# Ref_CLK.net
KiCad netlist of a schematic drawn in Altium Designer
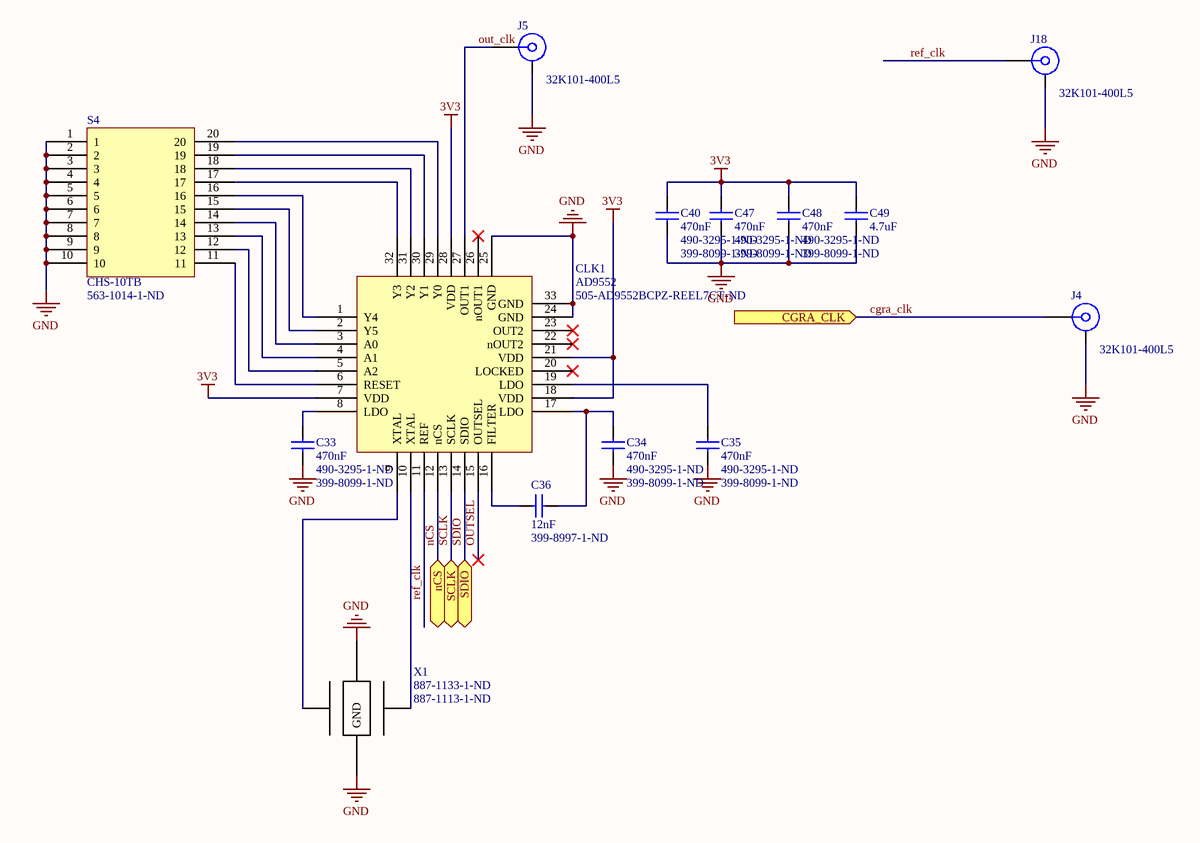
[diagram p0: Ref_CLK.SchDoc]

(export (version "E")
  (design (tool "Eeschema 10.0.6"))
  (components
    (comp (ref "C33")
      (value "CAP_470nF_1608mm_0603mil_1")
      (footprint "CAPC1005X06N")
      (description "0.47uF Capacitor")
      (fields
        (field (name "MANUFACTURER") "Murata")
        (field (name "MANUFACTURER PART NUMBER") "GRM155R61E225ME15D")
        (field (name "CAPACITANCE") "470nF")
        (field (name "SUPPLIER PART NUMBER 1") "490-3295-1-ND")
        (field (name "SUPPLIER PART NUMBER 2") "399-8099-1-ND")
      )
      (libsource (lib "CGRA_schlib") (part "CAP_470nF_1608mm_0603mil_1"))
    )
    (comp (ref "C34")
      (value "CAP_470nF_1608mm_0603mil_1")
      (footprint "CAPC1005X06N")
      (description "0.47uF Capacitor")
      (fields
        (field (name "MANUFACTURER") "Murata")
        (field (name "MANUFACTURER PART NUMBER") "GRM155R61E225ME15D")
        (field (name "CAPACITANCE") "470nF")
        (field (name "SUPPLIER PART NUMBER 1") "490-3295-1-ND")
        (field (name "SUPPLIER PART NUMBER 2") "399-8099-1-ND")
      )
      (libsource (lib "CGRA_schlib") (part "CAP_470nF_1608mm_0603mil_1"))
    )
    (comp (ref "C35")
      (value "CAP_470nF_1608mm_0603mil_1")
      (footprint "CAPC1005X06N")
      (description "0.47uF Capacitor")
      (fields
        (field (name "MANUFACTURER") "Murata")
        (field (name "MANUFACTURER PART NUMBER") "GRM155R61E225ME15D")
        (field (name "CAPACITANCE") "470nF")
        (field (name "SUPPLIER PART NUMBER 1") "490-3295-1-ND")
        (field (name "SUPPLIER PART NUMBER 2") "399-8099-1-ND")
      )
      (libsource (lib "CGRA_schlib") (part "CAP_470nF_1608mm_0603mil_1"))
    )
    (comp (ref "C36")
      (value "CAP_12nF_1608mm_0603mil")
      (footprint "CAPC1005X06N")
      (description "Multilayer Ceramic Capacitors MLCC - SMD/SMT 0402 2.2uF 25volts *Derate Voltage/Temp")
      (fields
        (field (name "MANUFACTURER") "Murata")
        (field (name "MANUFACTURER PART NUMBER") "GRM155R61E225ME15D")
        (field (name "CAPACITANCE") "12nF")
        (field (name "SUPPLIER PART NUMBER 1") "399-8997-1-ND")
      )
      (libsource (lib "CGRA_schlib") (part "CAP_12nF_1608mm_0603mil"))
    )
    (comp (ref "C40")
      (value "CAP_470nF_1608mm_0603mil_1")
      (footprint "CAPC1005X06N")
      (description "0.47uF Capacitor")
      (fields
        (field (name "MANUFACTURER") "Murata")
        (field (name "MANUFACTURER PART NUMBER") "GRM155R61E225ME15D")
        (field (name "CAPACITANCE") "470nF")
        (field (name "SUPPLIER PART NUMBER 1") "490-3295-1-ND")
        (field (name "SUPPLIER PART NUMBER 2") "399-8099-1-ND")
      )
      (libsource (lib "CGRA_schlib") (part "CAP_470nF_1608mm_0603mil_1"))
    )
    (comp (ref "C47")
      (value "CAP_470nF_1608mm_0603mil_1")
      (footprint "CAPC1005X06N")
      (description "0.47uF Capacitor")
      (fields
        (field (name "MANUFACTURER") "Murata")
        (field (name "MANUFACTURER PART NUMBER") "GRM155R61E225ME15D")
        (field (name "CAPACITANCE") "470nF")
        (field (name "SUPPLIER PART NUMBER 1") "490-3295-1-ND")
        (field (name "SUPPLIER PART NUMBER 2") "399-8099-1-ND")
      )
      (libsource (lib "CGRA_schlib") (part "CAP_470nF_1608mm_0603mil_1"))
    )
    (comp (ref "C48")
      (value "CAP_470nF_1608mm_0603mil_1")
      (footprint "CAPC1005X06N")
      (description "0.47uF Capacitor")
      (fields
        (field (name "MANUFACTURER") "Murata")
        (field (name "MANUFACTURER PART NUMBER") "GRM155R61E225ME15D")
        (field (name "CAPACITANCE") "470nF")
        (field (name "SUPPLIER PART NUMBER 1") "490-3295-1-ND")
        (field (name "SUPPLIER PART NUMBER 2") "399-8099-1-ND")
      )
      (libsource (lib "CGRA_schlib") (part "CAP_470nF_1608mm_0603mil_1"))
    )
    (comp (ref "C49")
      (value "CAP_4.7uF_0805_25V")
      (footprint "CAPC2012X14N")
      (description "Cap Ceramic 4.7uF 25V X5R 10% SMD 0805 85C Cardboard T/R")
      (fields
        (field (name "MANUFACTURER") "Samsung")
        (field (name "MANUFACTURER PART NUMBER") "CL21A475KACLRNC")
        (field (name "CAPACITANCE") "4.7uF")
      )
      (libsource (lib "CGRA_schlib") (part "CAP_4.7uF_0805_25V"))
    )
    (comp (ref "CLK1")
      (value "AD9552")
      (footprint "QFN50P500X500X80_HS-33N")
      (fields (field (name "SUPPLIER PART NUMBER 1") "505-AD9552BCPZ-REEL7CT-ND"))
      (libsource (lib "CGRA_schlib") (part "AD9552"))
    )
    (comp (ref "J4")
      (value "32K101-400L5")
      (footprint "ROS-32K101-400L5_V")
      (description "SMA Straight Jack, Up to 18 GHz, -55 to 155 degC")
      (libsource (lib "my_schsymbols") (part "32K101-400L5"))
    )
    (comp (ref "J5")
      (value "32K101-400L5")
      (footprint "ROS-32K101-400L5_V")
      (description "SMA Straight Jack, Up to 18 GHz, -55 to 155 degC")
      (libsource (lib "my_schsymbols") (part "32K101-400L5"))
    )
    (comp (ref "J18")
      (value "32K101-400L5")
      (footprint "ROS-32K101-400L5_V")
      (description "SMA Straight Jack, Up to 18 GHz, -55 to 155 degC")
      (libsource (lib "my_schsymbols") (part "32K101-400L5"))
    )
    (comp (ref "S4")
      (value "CHS-10TB")
      (footprint "SOIC127P800X250-20N")
      (fields (field (name "SUPPLIER PART NUMBER 1") "563-1014-1-ND"))
      (libsource (lib "CGRA_schlib") (part "CHS-10TB"))
    )
    (comp (ref "X1")
      (value "XTAL")
      (footprint "7M-26.000MAAJ-T footprint")
      (description "Crystal")
      (fields
        (field (name "MANUFACTURER") "Abracon")
        (field (name "MANUFACTURER PART NUMBER") "ABS07-120-32.768KHZ-T")
        (field (name "SUPPLIER PART NUMBER 1") "887-1133-1-ND")
        (field (name "SUPPLIER PART NUMBER 2") "887-1113-1-ND")
      )
      (libsource (lib "CGRA_schlib") (part "XTAL"))
    )
  )
  (nets
    (net (code "1") (name "/OUTSEL") (class "Default")
      (node (ref "CLK1") (pin "15") (pinfunction "OUTSEL_15") (pintype "passive+no_connect"))
    )
    (net (code "2") (name "/SCLK") (class "Default")
      (node (ref "CLK1") (pin "13") (pinfunction "SCLK_13") (pintype "passive"))
    )
    (net (code "3") (name "/SDIO") (class "Default")
      (node (ref "CLK1") (pin "14") (pinfunction "SDIO_14") (pintype "passive"))
    )
    (net (code "4") (name "/cgra_clk") (class "Default")
      (node (ref "J4") (pin "1") (pinfunction "1_1") (pintype "passive"))
    )
    (net (code "5") (name "/nCS") (class "Default")
      (node (ref "CLK1") (pin "12") (pinfunction "nCS_12") (pintype "passive"))
    )
    (net (code "6") (name "/out_clk") (class "Default")
      (node (ref "CLK1") (pin "27") (pinfunction "OUT1_27") (pintype "passive"))
      (node (ref "J5") (pin "1") (pinfunction "1_1") (pintype "passive"))
    )
    (net (code "7") (name "/ref_clk") (class "Default")
      (node (ref "CLK1") (pin "11") (pinfunction "REF_11") (pintype "passive"))
      (node (ref "J18") (pin "1") (pinfunction "1_1") (pintype "passive"))
    )
    (net (code "8") (name "3V3") (class "Default")
      (node (ref "C40") (pin "1") (pintype "passive"))
      (node (ref "C47") (pin "1") (pintype "passive"))
      (node (ref "C48") (pin "1") (pintype "passive"))
      (node (ref "C49") (pin "1") (pintype "passive"))
      (node (ref "CLK1") (pin "18") (pinfunction "VDD_18") (pintype "passive"))
      (node (ref "CLK1") (pin "21") (pinfunction "VDD_21") (pintype "passive"))
      (node (ref "CLK1") (pin "28") (pinfunction "VDD_28") (pintype "passive"))
      (node (ref "CLK1") (pin "7") (pinfunction "VDD_7") (pintype "passive"))
    )
    (net (code "9") (name "GND") (class "Default")
      (node (ref "C33") (pin "2") (pinfunction "2_2") (pintype "passive"))
      (node (ref "C34") (pin "2") (pinfunction "2_2") (pintype "passive"))
      (node (ref "C35") (pin "2") (pinfunction "2_2") (pintype "passive"))
      (node (ref "C40") (pin "2") (pinfunction "2_2") (pintype "passive"))
      (node (ref "C47") (pin "2") (pinfunction "2_2") (pintype "passive"))
      (node (ref "C48") (pin "2") (pinfunction "2_2") (pintype "passive"))
      (node (ref "C49") (pin "2") (pinfunction "2_2") (pintype "passive"))
      (node (ref "CLK1") (pin "24") (pinfunction "GND_24") (pintype "passive"))
      (node (ref "CLK1") (pin "25") (pinfunction "GND_25") (pintype "passive"))
      (node (ref "CLK1") (pin "33") (pinfunction "GND_33") (pintype "passive"))
      (node (ref "J18") (pin "MH") (pinfunction "MH_MH") (pintype "passive"))
      (node (ref "J4") (pin "MH") (pinfunction "MH_MH") (pintype "passive"))
      (node (ref "J5") (pin "MH") (pinfunction "MH_MH") (pintype "passive"))
      (node (ref "S4") (pin "1") (pinfunction "1_1") (pintype "passive"))
      (node (ref "S4") (pin "10") (pinfunction "10_10") (pintype "passive"))
      (node (ref "S4") (pin "2") (pinfunction "2_2") (pintype "passive"))
      (node (ref "S4") (pin "3") (pinfunction "3_3") (pintype "passive"))
      (node (ref "S4") (pin "4") (pinfunction "4_4") (pintype "passive"))
      (node (ref "S4") (pin "5") (pinfunction "5_5") (pintype "passive"))
      (node (ref "S4") (pin "6") (pinfunction "6_6") (pintype "passive"))
      (node (ref "S4") (pin "7") (pinfunction "7_7") (pintype "passive"))
      (node (ref "S4") (pin "8") (pinfunction "8_8") (pintype "passive"))
      (node (ref "S4") (pin "9") (pinfunction "9_9") (pintype "passive"))
      (node (ref "X1") (pin "2") (pinfunction "3_2") (pintype "passive"))
      (node (ref "X1") (pin "4") (pinfunction "GND_4") (pintype "passive"))
    )
    (net (code "10") (name "Net-(C33-Pad1)") (class "Default")
      (node (ref "C33") (pin "1") (pintype "passive"))
      (node (ref "CLK1") (pin "8") (pinfunction "LDO_8") (pintype "passive"))
    )
    (net (code "11") (name "Net-(C34-Pad1)") (class "Default")
      (node (ref "C34") (pin "1") (pintype "passive"))
      (node (ref "C36") (pin "2") (pinfunction "2_2") (pintype "passive"))
      (node (ref "CLK1") (pin "17") (pinfunction "LDO_17") (pintype "passive"))
    )
    (net (code "12") (name "Net-(C35-Pad1)") (class "Default")
      (node (ref "C35") (pin "1") (pintype "passive"))
      (node (ref "CLK1") (pin "19") (pinfunction "LDO_19") (pintype "passive"))
    )
    (net (code "13") (name "Net-(CLK1-A0)") (class "Default")
      (node (ref "CLK1") (pin "3") (pinfunction "A0_3") (pintype "passive"))
      (node (ref "S4") (pin "14") (pinfunction "14_14") (pintype "passive"))
    )
    (net (code "14") (name "Net-(CLK1-A1)") (class "Default")
      (node (ref "CLK1") (pin "4") (pinfunction "A1_4") (pintype "passive"))
      (node (ref "S4") (pin "13") (pinfunction "13_13") (pintype "passive"))
    )
    (net (code "15") (name "Net-(CLK1-A2)") (class "Default")
      (node (ref "CLK1") (pin "5") (pinfunction "A2_5") (pintype "passive"))
      (node (ref "S4") (pin "12") (pinfunction "12_12") (pintype "passive"))
    )
    (net (code "16") (name "Net-(CLK1-FILTER)") (class "Default")
      (node (ref "C36") (pin "1") (pintype "passive"))
      (node (ref "CLK1") (pin "16") (pinfunction "FILTER_16") (pintype "passive"))
    )
    (net (code "17") (name "Net-(CLK1-RESET)") (class "Default")
      (node (ref "CLK1") (pin "6") (pinfunction "RESET_6") (pintype "passive"))
      (node (ref "S4") (pin "11") (pinfunction "11_11") (pintype "passive"))
    )
    (net (code "18") (name "Net-(CLK1-Y0)") (class "Default")
      (node (ref "CLK1") (pin "29") (pinfunction "Y0_29") (pintype "passive"))
      (node (ref "S4") (pin "20") (pinfunction "20_20") (pintype "passive"))
    )
    (net (code "19") (name "Net-(CLK1-Y1)") (class "Default")
      (node (ref "CLK1") (pin "30") (pinfunction "Y1_30") (pintype "passive"))
      (node (ref "S4") (pin "19") (pinfunction "19_19") (pintype "passive"))
    )
    (net (code "20") (name "Net-(CLK1-Y2)") (class "Default")
      (node (ref "CLK1") (pin "31") (pinfunction "Y2_31") (pintype "passive"))
      (node (ref "S4") (pin "18") (pinfunction "18_18") (pintype "passive"))
    )
    (net (code "21") (name "Net-(CLK1-Y3)") (class "Default")
      (node (ref "CLK1") (pin "32") (pinfunction "Y3_32") (pintype "passive"))
      (node (ref "S4") (pin "17") (pinfunction "17_17") (pintype "passive"))
    )
    (net (code "22") (name "Net-(CLK1-Y4)") (class "Default")
      (node (ref "CLK1") (pin "1") (pinfunction "Y4_1") (pintype "passive"))
      (node (ref "S4") (pin "16") (pinfunction "16_16") (pintype "passive"))
    )
    (net (code "23") (name "Net-(CLK1-Y5)") (class "Default")
      (node (ref "CLK1") (pin "2") (pinfunction "Y5_2") (pintype "passive"))
      (node (ref "S4") (pin "15") (pinfunction "15_15") (pintype "passive"))
    )
    (net (code "24") (name "Net-(X1-XI)") (class "Default")
      (node (ref "CLK1") (pin "10") (pinfunction "XTAL_10") (pintype "passive"))
      (node (ref "X1") (pin "3") (pinfunction "XI_3") (pintype "passive"))
    )
    (net (code "25") (name "Net-(X1-XO)") (class "Default")
      (node (ref "CLK1") (pin "9") (pinfunction "XTAL_9") (pintype "passive"))
      (node (ref "X1") (pin "1") (pinfunction "XO_1") (pintype "passive"))
    )
    (net (code "26") (name "unconnected-(CLK1-LOCKED-Pad20)") (class "Default")
      (node (ref "CLK1") (pin "20") (pinfunction "LOCKED_20") (pintype "passive+no_connect"))
    )
    (net (code "27") (name "unconnected-(CLK1-OUT2-Pad23)") (class "Default")
      (node (ref "CLK1") (pin "23") (pinfunction "OUT2_23") (pintype "passive+no_connect"))
    )
    (net (code "28") (name "unconnected-(CLK1-nOUT1-Pad26)") (class "Default")
      (node (ref "CLK1") (pin "26") (pinfunction "nOUT1_26") (pintype "passive+no_connect"))
    )
    (net (code "29") (name "unconnected-(CLK1-nOUT2-Pad22)") (class "Default")
      (node (ref "CLK1") (pin "22") (pinfunction "nOUT2_22") (pintype "passive+no_connect"))
    )
  )
)
